# SSB_Transceiver_Buffer_Amplifier.net
KiCad netlist of a schematic drawn in EAGLE
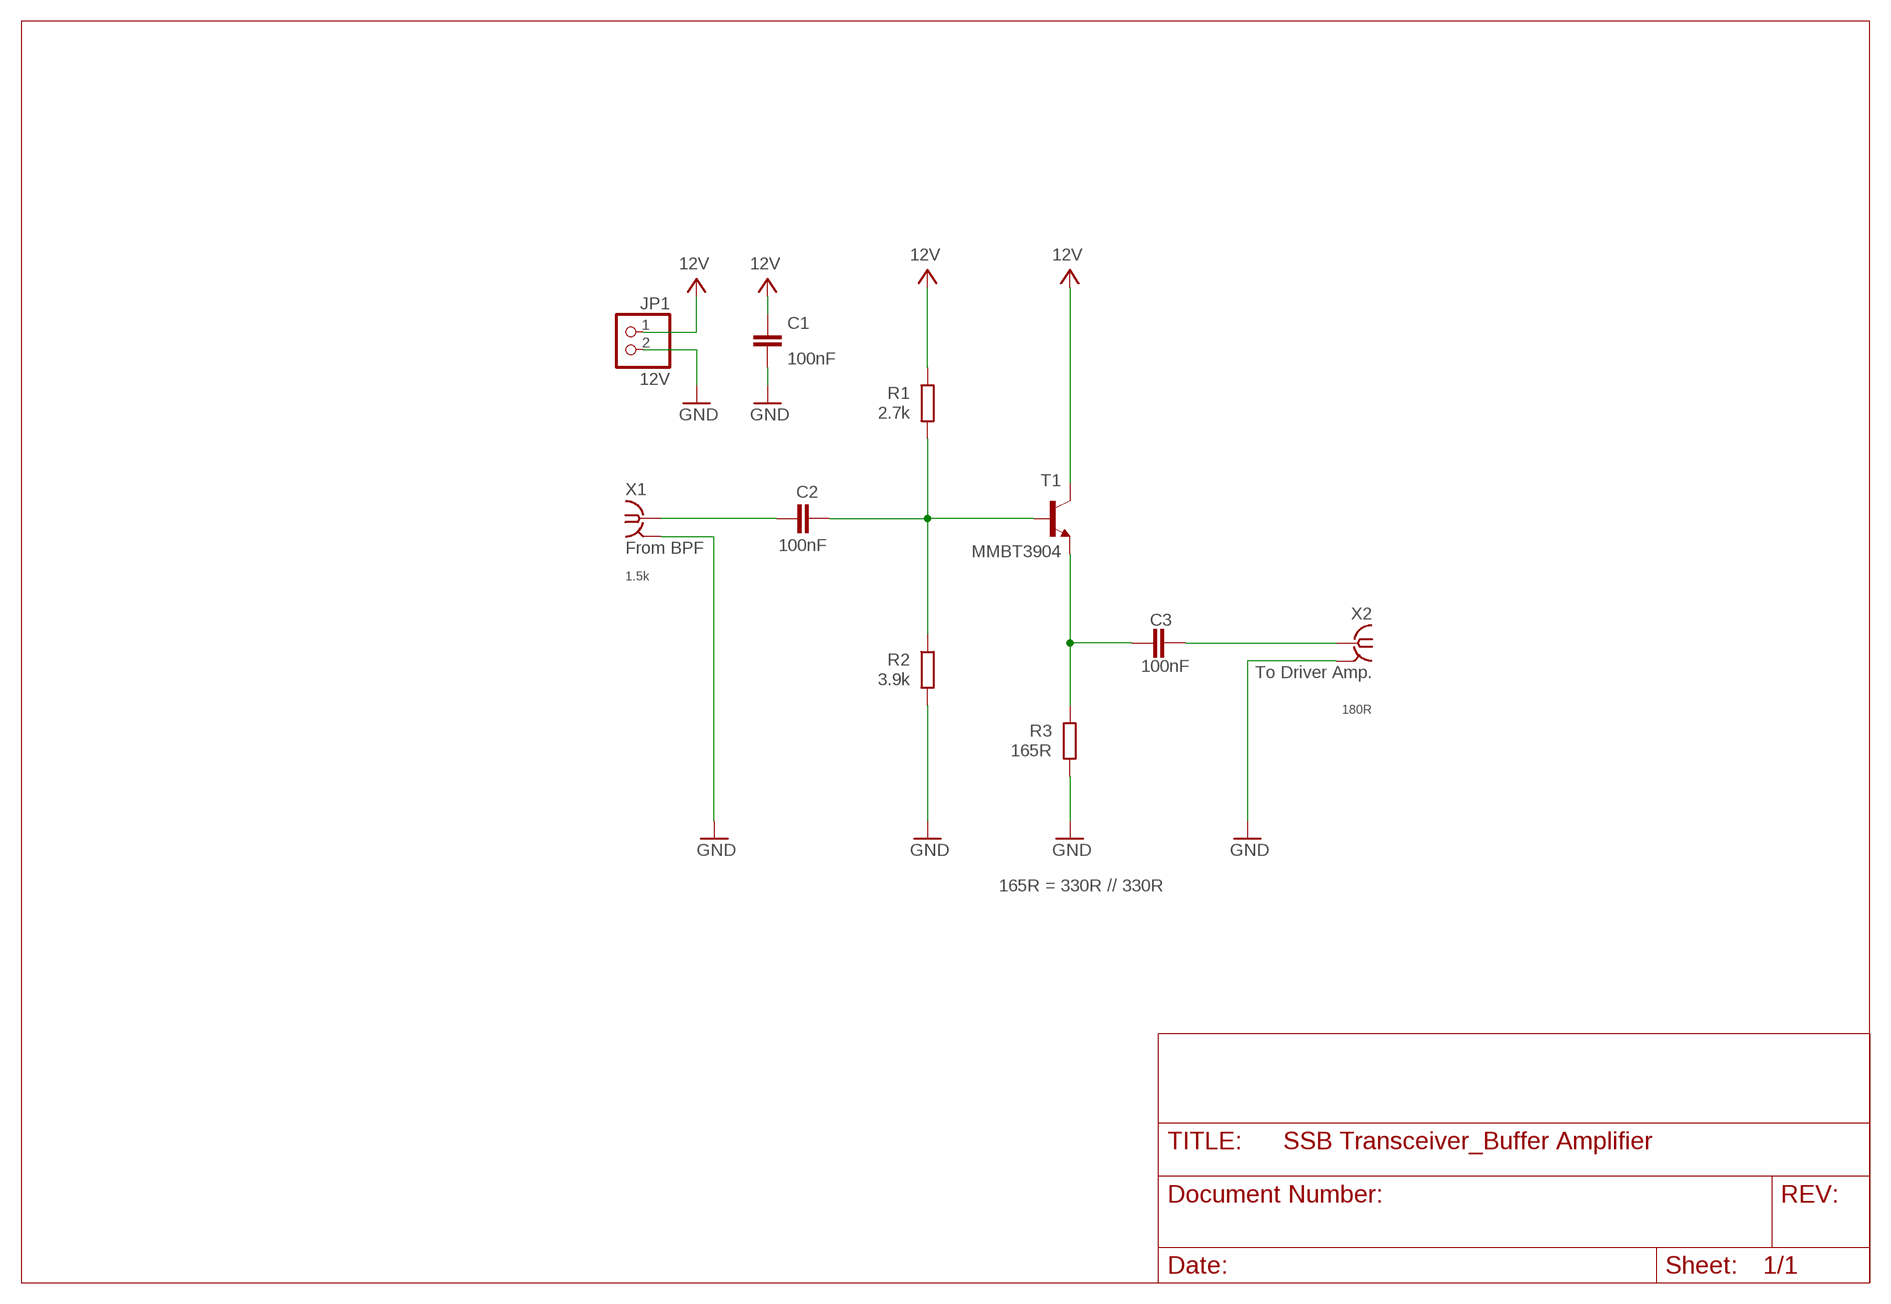
[diagram p0: schematic, sheet 1]

(export (version "E")
  (design (tool "Eeschema 10.0.6"))
  (components
    (comp (ref "C1")
      (value "100nF")
      (footprint "eagle-import:C0805")
      (libsource (lib "eagle-import") (part "C-EUC0805"))
    )
    (comp (ref "C2")
      (value "100nF")
      (footprint "eagle-import:C0805")
      (libsource (lib "eagle-import") (part "C-EUC0805"))
    )
    (comp (ref "C3")
      (value "100nF")
      (footprint "eagle-import:C0805")
      (libsource (lib "eagle-import") (part "C-EUC0805"))
    )
    (comp (ref "JP1")
      (value "12V")
      (footprint "eagle-import:1X02")
      (libsource (lib "eagle-import") (part "PINHD-1X2"))
    )
    (comp (ref "R1")
      (value "2.7k")
      (footprint "eagle-import:R0805")
      (libsource (lib "eagle-import") (part "R-EU_R0805"))
    )
    (comp (ref "R2")
      (value "3.9k")
      (footprint "eagle-import:R0805")
      (libsource (lib "eagle-import") (part "R-EU_R0805"))
    )
    (comp (ref "R3")
      (value "165R")
      (footprint "eagle-import:R0805")
      (libsource (lib "eagle-import") (part "R-EU_R0805"))
    )
    (comp (ref "T1")
      (value "MMBT3904")
      (footprint "eagle-import:SOT23-BEC")
      (libsource (lib "eagle-import") (part "-NPN-SOT23-BECMMBT3904LT1"))
    )
    (comp (ref "X1")
      (value "From BPF")
      (footprint "eagle-import:J502-ND-142-0711-821_826")
      (fields (field (name "MF") "JOHNSON COMPONENTS") (field (name "MPN") "142-0711-821"))
      (libsource (lib "eagle-import") (part "SMA-PCB-CON142-0711-821/826"))
    )
    (comp (ref "X2")
      (value "To Driver Amp.")
      (footprint "eagle-import:J502-ND-142-0711-821_826")
      (fields (field (name "MF") "JOHNSON COMPONENTS") (field (name "MPN") "142-0711-821"))
      (libsource (lib "eagle-import") (part "SMA-PCB-CON142-0711-821/826"))
    )
  )
  (nets
    (net (code "1") (name "12V") (class "Default")
      (node (ref "C1") (pin "2") (pinfunction "2_2") (pintype "passive"))
      (node (ref "JP1") (pin "1") (pinfunction "1_1") (pintype "passive"))
      (node (ref "R1") (pin "1") (pinfunction "1_1") (pintype "passive"))
      (node (ref "T1") (pin "C") (pinfunction "C_C") (pintype "passive"))
    )
    (net (code "2") (name "GND") (class "Default")
      (node (ref "C1") (pin "1") (pinfunction "1_1") (pintype "passive"))
      (node (ref "JP1") (pin "2") (pinfunction "2_2") (pintype "passive"))
      (node (ref "R2") (pin "2") (pinfunction "2_2") (pintype "passive"))
      (node (ref "R3") (pin "2") (pinfunction "2_2") (pintype "passive"))
      (node (ref "X1") (pin "G@1") (pinfunction "GND_G@1") (pintype "passive"))
      (node (ref "X1") (pin "G@2") (pinfunction "GND_G@2") (pintype "passive"))
      (node (ref "X1") (pin "G@3") (pinfunction "GND_G@3") (pintype "passive"))
      (node (ref "X1") (pin "G@4") (pinfunction "GND_G@4") (pintype "passive"))
      (node (ref "X2") (pin "G@1") (pinfunction "GND_G@1") (pintype "passive"))
      (node (ref "X2") (pin "G@2") (pinfunction "GND_G@2") (pintype "passive"))
      (node (ref "X2") (pin "G@3") (pinfunction "GND_G@3") (pintype "passive"))
      (node (ref "X2") (pin "G@4") (pinfunction "GND_G@4") (pintype "passive"))
    )
    (net (code "3") (name "Net-(C2-Pad2)") (class "Default")
      (node (ref "C2") (pin "2") (pinfunction "2_2") (pintype "passive"))
      (node (ref "R1") (pin "2") (pinfunction "2_2") (pintype "passive"))
      (node (ref "R2") (pin "1") (pinfunction "1_1") (pintype "passive"))
      (node (ref "T1") (pin "B") (pinfunction "B_B") (pintype "passive"))
    )
    (net (code "4") (name "Net-(C3-Pad2)") (class "Default")
      (node (ref "C3") (pin "2") (pinfunction "2_2") (pintype "passive"))
      (node (ref "R3") (pin "1") (pinfunction "1_1") (pintype "passive"))
      (node (ref "T1") (pin "E") (pinfunction "E_E") (pintype "passive"))
    )
    (net (code "5") (name "Net-(X1-RF)") (class "Default")
      (node (ref "C2") (pin "1") (pinfunction "1_1") (pintype "passive"))
      (node (ref "X1") (pin "1") (pinfunction "RF_1") (pintype "passive"))
    )
    (net (code "6") (name "Net-(X2-RF)") (class "Default")
      (node (ref "C3") (pin "1") (pinfunction "1_1") (pintype "passive"))
      (node (ref "X2") (pin "1") (pinfunction "RF_1") (pintype "passive"))
    )
  )
)
